# AEBS_component_Rear.net
KiCad netlist of a schematic drawn in Altium Designer
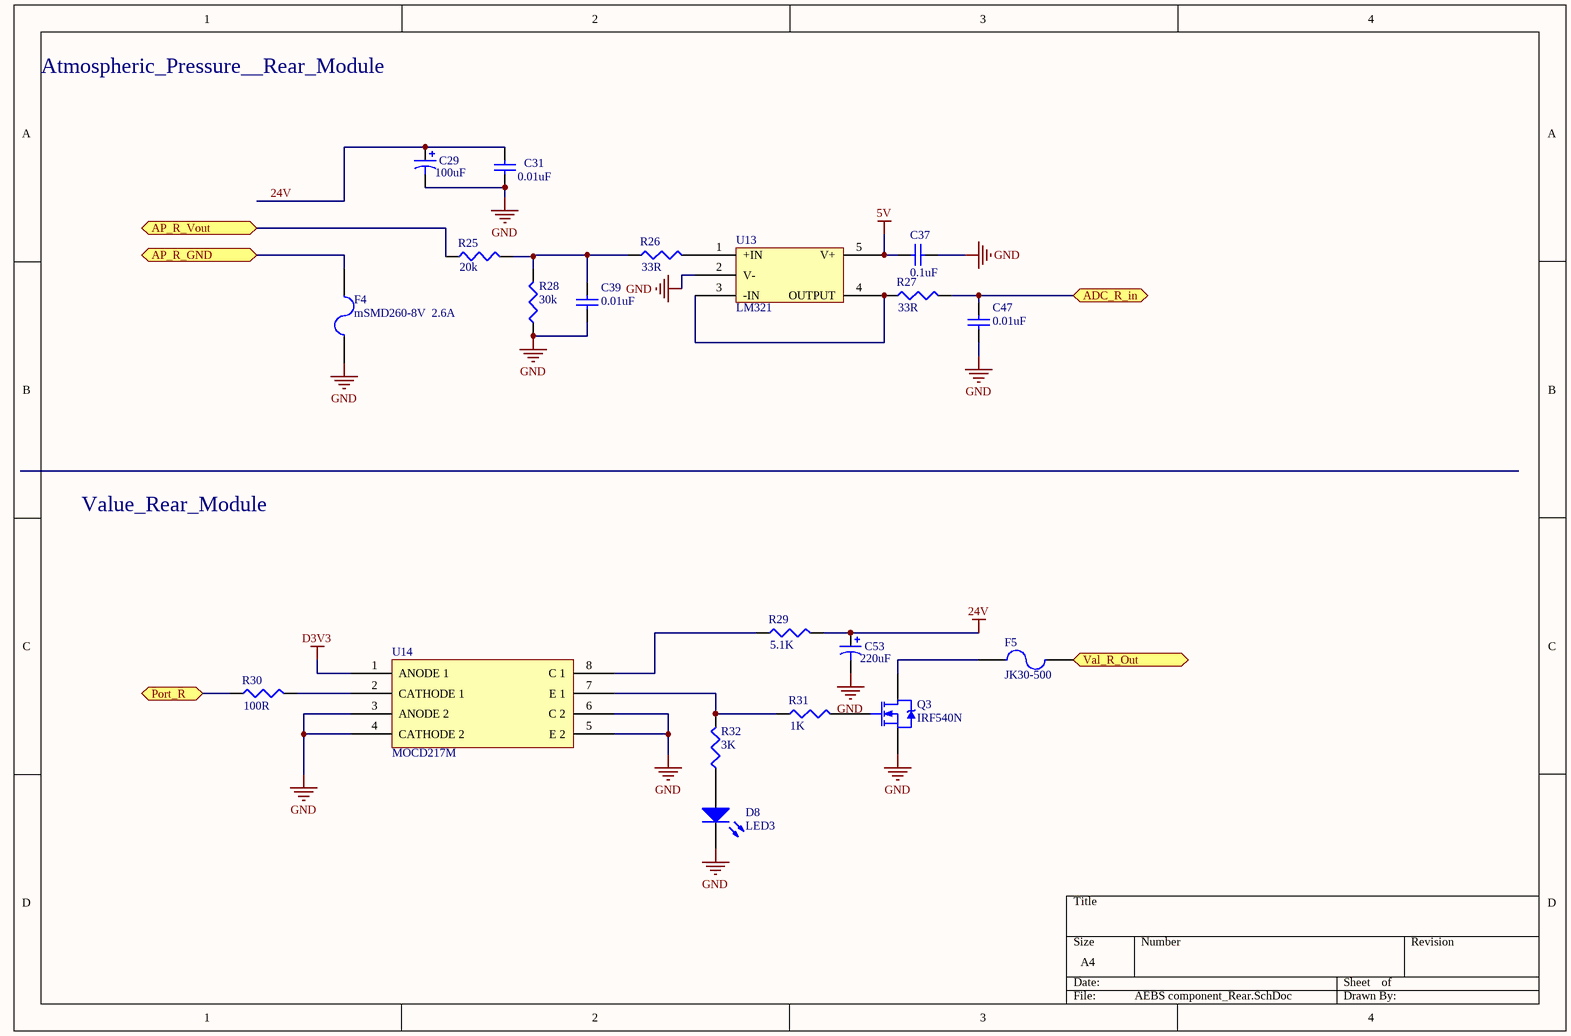
[diagram p0: AEBS component_Rear.SchDoc]

(export (version "E")
  (design (tool "Eeschema 10.0.6"))
  (components
    (comp (ref "C29")
      (value "100uF")
      (footprint "C0805")
      (description "Polarized Capacitor (Surface Mount)")
      (fields (field (name "Comment") "Cap Pol3") (field (name "PUBLISHER") "Altium Limited"))
      (libsource (lib "Miscellaneous Devices") (part "Cap Pol3"))
    )
    (comp (ref "C31")
      (value "0.01uF")
      (footprint "C1206")
      (description "Capacitor (Semiconductor SIM Model)")
      (fields (field (name "Comment") "Cap Semi") (field (name "PUBLISHER") "Altium Limited"))
      (libsource (lib "Miscellaneous Devices") (part "Cap Semi"))
    )
    (comp (ref "C37")
      (value "0.1uF")
      (footprint "1608[0603]")
      (description "Capacitor (Semiconductor SIM Model)")
      (fields (field (name "Comment") "Cap Semi") (field (name "PUBLISHER") "Altium Limited"))
      (libsource (lib "Miscellaneous Devices") (part "Cap Semi"))
    )
    (comp (ref "C39")
      (value "0.01uF")
      (footprint "1608[0603]")
      (description "Capacitor (Semiconductor SIM Model)")
      (fields (field (name "Comment") "Cap Semi") (field (name "PUBLISHER") "Altium Limited"))
      (libsource (lib "Miscellaneous Devices") (part "Cap Semi"))
    )
    (comp (ref "C47")
      (value "0.01uF")
      (footprint "1608[0603]")
      (description "Capacitor (Semiconductor SIM Model)")
      (fields (field (name "Comment") "Cap Semi") (field (name "PUBLISHER") "Altium Limited"))
      (libsource (lib "Miscellaneous Devices") (part "Cap Semi"))
    )
    (comp (ref "C53")
      (value "220uF")
      (footprint "hg:Cap_pol_8*10.2")
      (description "Polarized Capacitor (Surface Mount)")
      (fields (field (name "Comment") "Cap Pol3") (field (name "PUBLISHER") "Altium Limited"))
      (libsource (lib "Miscellaneous Devices") (part "Cap Pol3"))
    )
    (comp (ref "D8")
      (value "LED3")
      (footprint "hg:1206")
      (description "Typical BLUE SiC LED")
      (fields (field (name "PUBLISHER") "Altium Limited"))
      (libsource (lib "Miscellaneous Devices") (part "LED3"))
    )
    (comp (ref "F4")
      (value "mSMD260-8V  2.6A")
      (footprint "1812")
      (description "Fuse")
      (fields (field (name "PUBLISHER") "Altium Limited"))
      (libsource (lib "Miscellaneous Devices") (part "Fuse 2"))
    )
    (comp (ref "F5")
      (value "JK30-500")
      (footprint "hg:JK30-500")
      (description "Fuse")
      (fields (field (name "PUBLISHER") "Altium Limited"))
      (libsource (lib "Miscellaneous Devices") (part "Fuse 2"))
    )
    (comp (ref "Q3")
      (value "IRF540N")
      (footprint "TO-220AB")
      (description "N-Channel Power MOSFET")
      (fields (field (name "PUBLISHER") "Altium Limited"))
      (libsource (lib "Miscellaneous Devices") (part "NMOS-2"))
    )
    (comp (ref "R25")
      (value "20k")
      (footprint "J1-0603")
      (description "Resistor")
      (fields (field (name "Comment") "Res3") (field (name "PUBLISHER") "Altium Limited"))
      (libsource (lib "Miscellaneous Devices") (part "Res3"))
    )
    (comp (ref "R26")
      (value "33R")
      (footprint "J1-0603")
      (description "Resistor")
      (fields (field (name "Comment") "Res3") (field (name "PUBLISHER") "Altium Limited"))
      (libsource (lib "Miscellaneous Devices") (part "Res3"))
    )
    (comp (ref "R27")
      (value "33R")
      (footprint "J1-0603")
      (description "Resistor")
      (fields (field (name "Comment") "Res3") (field (name "PUBLISHER") "Altium Limited"))
      (libsource (lib "Miscellaneous Devices") (part "Res3"))
    )
    (comp (ref "R28")
      (value "30k")
      (footprint "J1-0603")
      (description "Resistor")
      (fields (field (name "Comment") "Res3") (field (name "PUBLISHER") "Altium Limited"))
      (libsource (lib "Miscellaneous Devices") (part "Res3"))
    )
    (comp (ref "R29")
      (value "5.1K")
      (footprint "J1-0603")
      (description "Resistor")
      (fields (field (name "Comment") "Res3") (field (name "PUBLISHER") "Altium Limited"))
      (libsource (lib "Miscellaneous Devices") (part "Res3"))
    )
    (comp (ref "R30")
      (value "100R")
      (footprint "J1-0603")
      (description "Resistor")
      (fields (field (name "Comment") "Res3") (field (name "PUBLISHER") "Altium Limited"))
      (libsource (lib "Miscellaneous Devices") (part "Res3"))
    )
    (comp (ref "R31")
      (value "1K")
      (footprint "J1-0603")
      (description "Resistor")
      (fields (field (name "Comment") "Res3") (field (name "PUBLISHER") "Altium Limited"))
      (libsource (lib "Miscellaneous Devices") (part "Res3"))
    )
    (comp (ref "R32")
      (value "3K")
      (footprint "J1-0603")
      (description "Resistor")
      (fields (field (name "Comment") "Res3") (field (name "PUBLISHER") "Altium Limited"))
      (libsource (lib "Miscellaneous Devices") (part "Res3"))
    )
    (comp (ref "U13") (value "LM321") (footprint "hg:LM321") (libsource (lib "hg") (part "LM321")))
    (comp (ref "U14") (value "MOCD217M") (footprint "hg:MOCD217M") (libsource (lib "hg") (part "MOCD217M")))
  )
  (nets
    (net (code "1") (name "/ADC_R_in") (class "Default")
      (node (ref "C47") (pin "2") (pinfunction "2_2") (pintype "passive"))
      (node (ref "R27") (pin "2") (pinfunction "2_2") (pintype "passive"))
    )
    (net (code "2") (name "/AP_R_GND") (class "Default")
      (node (ref "F4") (pin "1") (pinfunction "1_1") (pintype "passive"))
    )
    (net (code "3") (name "/AP_R_Vout") (class "Default")
      (node (ref "R25") (pin "1") (pinfunction "1_1") (pintype "passive"))
    )
    (net (code "4") (name "/Port_R") (class "Default")
      (node (ref "R30") (pin "1") (pinfunction "1_1") (pintype "passive"))
    )
    (net (code "5") (name "/Val_R_Out") (class "Default")
      (node (ref "F5") (pin "2") (pinfunction "2_2") (pintype "passive"))
    )
    (net (code "6") (name "5V") (class "Default")
      (node (ref "C37") (pin "2") (pinfunction "2_2") (pintype "passive"))
      (node (ref "U13") (pin "5") (pinfunction "V+_5") (pintype "passive"))
    )
    (net (code "7") (name "24V") (class "Default")
      (node (ref "C29") (pin "1") (pinfunction "1_1") (pintype "passive"))
      (node (ref "C31") (pin "1") (pinfunction "1_1") (pintype "passive"))
      (node (ref "C53") (pin "1") (pinfunction "1_1") (pintype "passive"))
      (node (ref "R29") (pin "2") (pinfunction "2_2") (pintype "passive"))
    )
    (net (code "8") (name "D3V3") (class "Default")
      (node (ref "U14") (pin "1") (pinfunction "ANODE_1_1") (pintype "passive"))
    )
    (net (code "9") (name "GND") (class "Default")
      (node (ref "C29") (pin "2") (pinfunction "2_2") (pintype "passive"))
      (node (ref "C31") (pin "2") (pinfunction "2_2") (pintype "passive"))
      (node (ref "C37") (pin "1") (pinfunction "1_1") (pintype "passive"))
      (node (ref "C39") (pin "1") (pinfunction "1_1") (pintype "passive"))
      (node (ref "C47") (pin "1") (pinfunction "1_1") (pintype "passive"))
      (node (ref "C53") (pin "2") (pinfunction "2_2") (pintype "passive"))
      (node (ref "D8") (pin "2") (pinfunction "K_2") (pintype "passive"))
      (node (ref "F4") (pin "2") (pinfunction "2_2") (pintype "passive"))
      (node (ref "Q3") (pin "3") (pinfunction "S_3") (pintype "passive"))
      (node (ref "R28") (pin "1") (pinfunction "1_1") (pintype "passive"))
      (node (ref "U13") (pin "2") (pinfunction "V-_2") (pintype "passive"))
      (node (ref "U14") (pin "3") (pinfunction "ANODE_2_3") (pintype "passive"))
      (node (ref "U14") (pin "4") (pinfunction "CATHODE_2_4") (pintype "passive"))
      (node (ref "U14") (pin "5") (pinfunction "E_2_5") (pintype "passive"))
      (node (ref "U14") (pin "6") (pinfunction "C_2_6") (pintype "passive"))
    )
    (net (code "10") (name "Net-(C39-Pad2)") (class "Default")
      (node (ref "C39") (pin "2") (pinfunction "2_2") (pintype "passive"))
      (node (ref "R25") (pin "2") (pinfunction "2_2") (pintype "passive"))
      (node (ref "R26") (pin "1") (pinfunction "1_1") (pintype "passive"))
      (node (ref "R28") (pin "2") (pinfunction "2_2") (pintype "passive"))
    )
    (net (code "11") (name "Net-(D8-A)") (class "Default")
      (node (ref "D8") (pin "1") (pinfunction "A_1") (pintype "passive"))
      (node (ref "R32") (pin "1") (pinfunction "1_1") (pintype "passive"))
    )
    (net (code "12") (name "Net-(Q3-D)") (class "Default")
      (node (ref "F5") (pin "1") (pinfunction "1_1") (pintype "passive"))
      (node (ref "Q3") (pin "2") (pinfunction "D_2") (pintype "passive"))
    )
    (net (code "13") (name "Net-(Q3-G)") (class "Default")
      (node (ref "Q3") (pin "1") (pinfunction "G_1") (pintype "passive"))
      (node (ref "R31") (pin "2") (pinfunction "2_2") (pintype "passive"))
    )
    (net (code "14") (name "Net-(U13-+IN)") (class "Default")
      (node (ref "R26") (pin "2") (pinfunction "2_2") (pintype "passive"))
      (node (ref "U13") (pin "1") (pinfunction "+IN_1") (pintype "passive"))
    )
    (net (code "15") (name "Net-(U13--IN)") (class "Default")
      (node (ref "R27") (pin "1") (pinfunction "1_1") (pintype "passive"))
      (node (ref "U13") (pin "3") (pinfunction "-IN_3") (pintype "passive"))
      (node (ref "U13") (pin "4") (pinfunction "OUTPUT_4") (pintype "passive"))
    )
    (net (code "16") (name "Net-(U14-CATHODE_1)") (class "Default")
      (node (ref "R30") (pin "2") (pinfunction "2_2") (pintype "passive"))
      (node (ref "U14") (pin "2") (pinfunction "CATHODE_1_2") (pintype "passive"))
    )
    (net (code "17") (name "Net-(U14-C_1)") (class "Default")
      (node (ref "R29") (pin "1") (pinfunction "1_1") (pintype "passive"))
      (node (ref "U14") (pin "8") (pinfunction "C_1_8") (pintype "passive"))
    )
    (net (code "18") (name "Net-(U14-E_1)") (class "Default")
      (node (ref "R31") (pin "1") (pinfunction "1_1") (pintype "passive"))
      (node (ref "R32") (pin "2") (pinfunction "2_2") (pintype "passive"))
      (node (ref "U14") (pin "7") (pinfunction "E_1_7") (pintype "passive"))
    )
  )
)
